# H3BR7.net
KiCad netlist of a schematic drawn in EAGLE
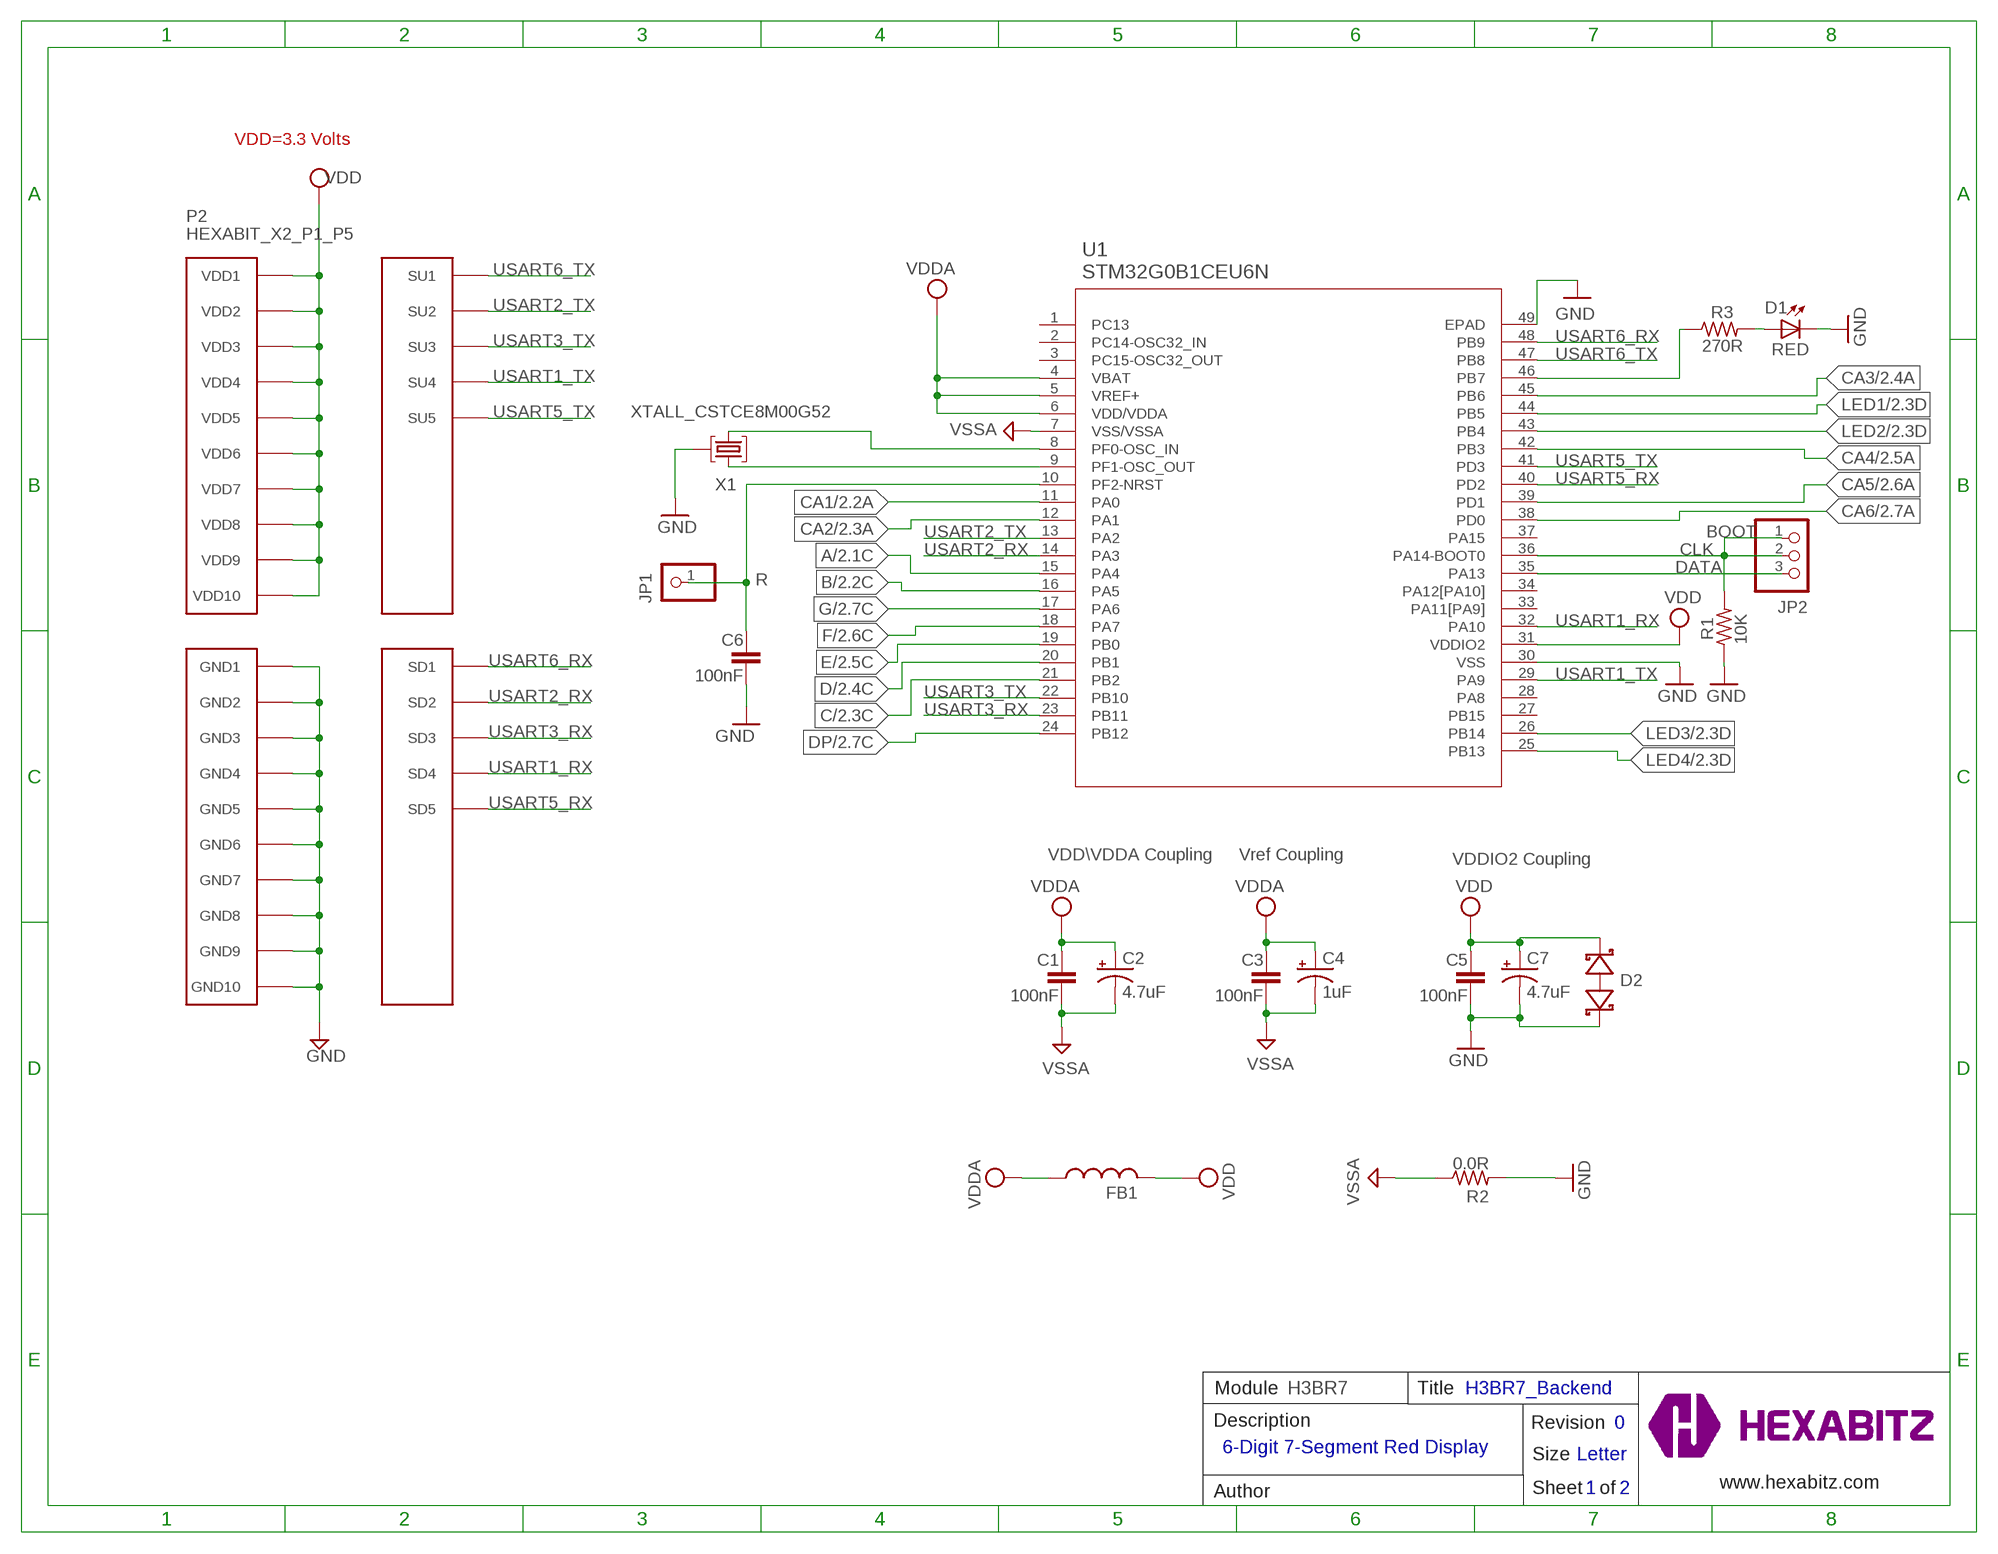
[diagram p0: schematic, sheet 1]
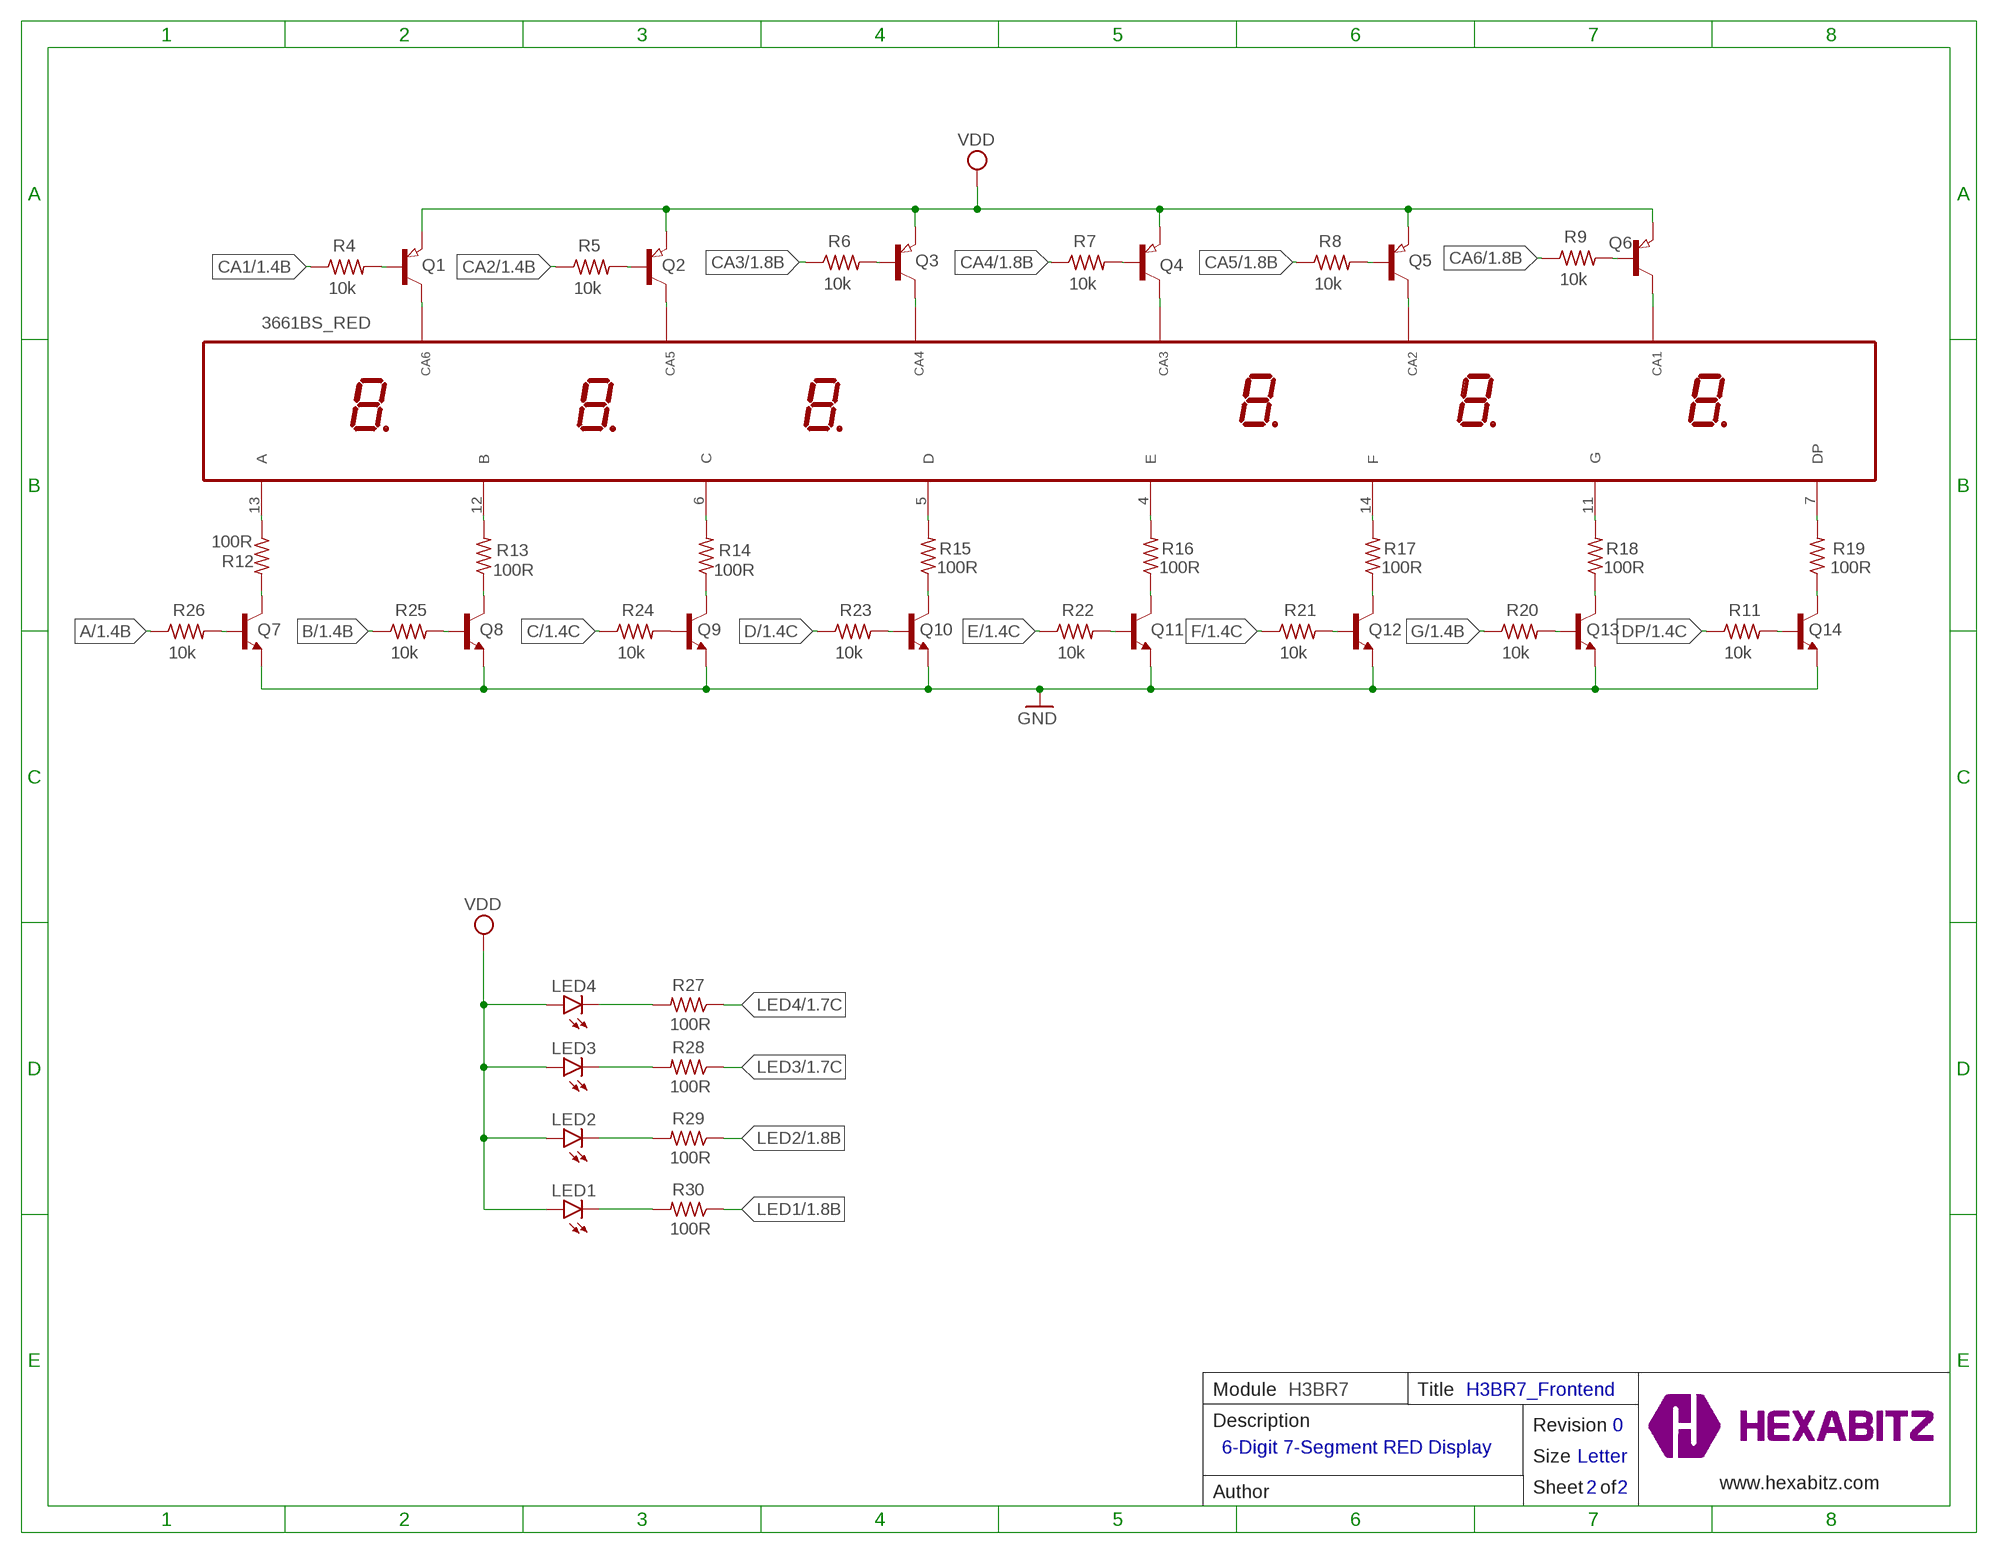
[diagram p1: schematic, sheet 2]

(export (version "E")
  (design (tool "Eeschema 10.0.6"))
  (components
    (comp (ref "3661BS")
      (value "3661BS_RED")
      (footprint "eagle-import:3661BS")
      (libsource (lib "eagle-import") (part "3661BS_RED"))
    )
    (comp (ref "LED1")
      (value "LED-3MM3MM")
      (footprint "eagle-import:LED3MM")
      (libsource (lib "eagle-import") (part "LED-3MM3MM"))
    )
    (comp (ref "LED2")
      (value "LED-3MM3MM")
      (footprint "eagle-import:LED3MM")
      (libsource (lib "eagle-import") (part "LED-3MM3MM"))
    )
    (comp (ref "LED3")
      (value "LED-3MM3MM")
      (footprint "eagle-import:LED3MM")
      (libsource (lib "eagle-import") (part "LED-3MM3MM"))
    )
    (comp (ref "LED4")
      (value "LED-3MM3MM")
      (footprint "eagle-import:LED3MM")
      (libsource (lib "eagle-import") (part "LED-3MM3MM"))
    )
    (comp (ref "Q1")
      (value "SEMICON-SMD-IPC_PNP-TRANSISTOR_SOT23")
      (footprint "eagle-import:SEMICON-SMD-IPC_SOT23")
      (libsource (lib "eagle-import") (part "SEMICON-SMD-IPC_PNP-TRANSISTOR_SOT23"))
    )
    (comp (ref "Q2")
      (value "SEMICON-SMD-IPC_PNP-TRANSISTOR_SOT23")
      (footprint "eagle-import:SEMICON-SMD-IPC_SOT23")
      (libsource (lib "eagle-import") (part "SEMICON-SMD-IPC_PNP-TRANSISTOR_SOT23"))
    )
    (comp (ref "Q3")
      (value "SEMICON-SMD-IPC_PNP-TRANSISTOR_SOT23")
      (footprint "eagle-import:SEMICON-SMD-IPC_SOT23")
      (libsource (lib "eagle-import") (part "SEMICON-SMD-IPC_PNP-TRANSISTOR_SOT23"))
    )
    (comp (ref "Q4")
      (value "SEMICON-SMD-IPC_PNP-TRANSISTOR_SOT23")
      (footprint "eagle-import:SEMICON-SMD-IPC_SOT23")
      (libsource (lib "eagle-import") (part "SEMICON-SMD-IPC_PNP-TRANSISTOR_SOT23"))
    )
    (comp (ref "Q5")
      (value "SEMICON-SMD-IPC_PNP-TRANSISTOR_SOT23")
      (footprint "eagle-import:SEMICON-SMD-IPC_SOT23")
      (libsource (lib "eagle-import") (part "SEMICON-SMD-IPC_PNP-TRANSISTOR_SOT23"))
    )
    (comp (ref "Q6")
      (value "SEMICON-SMD-IPC_PNP-TRANSISTOR_SOT23")
      (footprint "eagle-import:SEMICON-SMD-IPC_SOT23")
      (libsource (lib "eagle-import") (part "SEMICON-SMD-IPC_PNP-TRANSISTOR_SOT23"))
    )
    (comp (ref "Q7")
      (value "MMBT3904LT1")
      (footprint "eagle-import:MMBT3904LT1")
      (libsource (lib "eagle-import") (part "MMBT3904LT1"))
    )
    (comp (ref "Q8")
      (value "MMBT3904LT1")
      (footprint "eagle-import:MMBT3904LT1")
      (libsource (lib "eagle-import") (part "MMBT3904LT1"))
    )
    (comp (ref "Q9")
      (value "MMBT3904LT1")
      (footprint "eagle-import:MMBT3904LT1")
      (libsource (lib "eagle-import") (part "MMBT3904LT1"))
    )
    (comp (ref "Q10")
      (value "MMBT3904LT1")
      (footprint "eagle-import:MMBT3904LT1")
      (libsource (lib "eagle-import") (part "MMBT3904LT1"))
    )
    (comp (ref "Q11")
      (value "MMBT3904LT1")
      (footprint "eagle-import:MMBT3904LT1")
      (libsource (lib "eagle-import") (part "MMBT3904LT1"))
    )
    (comp (ref "Q12")
      (value "MMBT3904LT1")
      (footprint "eagle-import:MMBT3904LT1")
      (libsource (lib "eagle-import") (part "MMBT3904LT1"))
    )
    (comp (ref "Q13")
      (value "MMBT3904LT1")
      (footprint "eagle-import:MMBT3904LT1")
      (libsource (lib "eagle-import") (part "MMBT3904LT1"))
    )
    (comp (ref "Q14")
      (value "MMBT3904LT1")
      (footprint "eagle-import:MMBT3904LT1")
      (libsource (lib "eagle-import") (part "MMBT3904LT1"))
    )
    (comp (ref "R4")
      (value "10k")
      (footprint "eagle-import:R-0603")
      (libsource (lib "eagle-import") (part "R-0603"))
    )
    (comp (ref "R5")
      (value "10k")
      (footprint "eagle-import:R-0603")
      (libsource (lib "eagle-import") (part "R-0603"))
    )
    (comp (ref "R6")
      (value "10k")
      (footprint "eagle-import:R-0603")
      (libsource (lib "eagle-import") (part "R-0603"))
    )
    (comp (ref "R7")
      (value "10k")
      (footprint "eagle-import:R-0603")
      (libsource (lib "eagle-import") (part "R-0603"))
    )
    (comp (ref "R8")
      (value "10k")
      (footprint "eagle-import:R-0603")
      (libsource (lib "eagle-import") (part "R-0603"))
    )
    (comp (ref "R9")
      (value "10k")
      (footprint "eagle-import:R-0603")
      (libsource (lib "eagle-import") (part "R-0603"))
    )
    (comp (ref "R11")
      (value "10k")
      (footprint "eagle-import:R-0603")
      (libsource (lib "eagle-import") (part "R-0603"))
    )
    (comp (ref "R12")
      (value "100R")
      (footprint "eagle-import:R-0603")
      (libsource (lib "eagle-import") (part "R-0603"))
    )
    (comp (ref "R13")
      (value "100R")
      (footprint "eagle-import:R-0603")
      (libsource (lib "eagle-import") (part "R-0603"))
    )
    (comp (ref "R14")
      (value "100R")
      (footprint "eagle-import:R-0603")
      (libsource (lib "eagle-import") (part "R-0603"))
    )
    (comp (ref "R15")
      (value "100R")
      (footprint "eagle-import:R-0603")
      (libsource (lib "eagle-import") (part "R-0603"))
    )
    (comp (ref "R16")
      (value "100R")
      (footprint "eagle-import:R-0603")
      (libsource (lib "eagle-import") (part "R-0603"))
    )
    (comp (ref "R17")
      (value "100R")
      (footprint "eagle-import:R-0603")
      (libsource (lib "eagle-import") (part "R-0603"))
    )
    (comp (ref "R18")
      (value "100R")
      (footprint "eagle-import:R-0603")
      (libsource (lib "eagle-import") (part "R-0603"))
    )
    (comp (ref "R19")
      (value "100R")
      (footprint "eagle-import:R-0603")
      (libsource (lib "eagle-import") (part "R-0603"))
    )
    (comp (ref "R20")
      (value "10k")
      (footprint "eagle-import:R-0603")
      (libsource (lib "eagle-import") (part "R-0603"))
    )
    (comp (ref "R21")
      (value "10k")
      (footprint "eagle-import:R-0603")
      (libsource (lib "eagle-import") (part "R-0603"))
    )
    (comp (ref "R22")
      (value "10k")
      (footprint "eagle-import:R-0603")
      (libsource (lib "eagle-import") (part "R-0603"))
    )
    (comp (ref "R23")
      (value "10k")
      (footprint "eagle-import:R-0603")
      (libsource (lib "eagle-import") (part "R-0603"))
    )
    (comp (ref "R24")
      (value "10k")
      (footprint "eagle-import:R-0603")
      (libsource (lib "eagle-import") (part "R-0603"))
    )
    (comp (ref "R25")
      (value "10k")
      (footprint "eagle-import:R-0603")
      (libsource (lib "eagle-import") (part "R-0603"))
    )
    (comp (ref "R26")
      (value "10k")
      (footprint "eagle-import:R-0603")
      (libsource (lib "eagle-import") (part "R-0603"))
    )
    (comp (ref "R27")
      (value "100R")
      (footprint "eagle-import:R-0603")
      (libsource (lib "eagle-import") (part "R-0603"))
    )
    (comp (ref "R28")
      (value "100R")
      (footprint "eagle-import:R-0603")
      (libsource (lib "eagle-import") (part "R-0603"))
    )
    (comp (ref "R29")
      (value "100R")
      (footprint "eagle-import:R-0603")
      (libsource (lib "eagle-import") (part "R-0603"))
    )
    (comp (ref "R30")
      (value "100R")
      (footprint "eagle-import:R-0603")
      (libsource (lib "eagle-import") (part "R-0603"))
    )
    (comp (ref "TRIMBLE-LOGO1")
      (value "HEXA-LOGO")
      (footprint "eagle-import:HEXA-LOGO")
      (libsource (lib "eagle-import") (part "HEXA-LOGO"))
    )
    (comp (ref "C1")
      (value "100nF")
      (footprint "eagle-import:C-0603")
      (libsource (lib "eagle-import") (part "C-0603"))
    )
    (comp (ref "C2")
      (value "4.7uF")
      (footprint "eagle-import:C-0805-POL")
      (libsource (lib "eagle-import") (part "C-0805-POL"))
    )
    (comp (ref "C3")
      (value "100nF")
      (footprint "eagle-import:C-0603")
      (libsource (lib "eagle-import") (part "C-0603"))
    )
    (comp (ref "C4")
      (value "1uF")
      (footprint "eagle-import:C-0805-POL")
      (libsource (lib "eagle-import") (part "C-0805-POL"))
    )
    (comp (ref "C5")
      (value "100nF")
      (footprint "eagle-import:C-0603")
      (libsource (lib "eagle-import") (part "C-0603"))
    )
    (comp (ref "C6")
      (value "100nF")
      (footprint "eagle-import:C-0603")
      (libsource (lib "eagle-import") (part "C-0603"))
    )
    (comp (ref "C7")
      (value "4.7uF")
      (footprint "eagle-import:C-0805-POL")
      (libsource (lib "eagle-import") (part "C-0805-POL"))
    )
    (comp (ref "D1")
      (value "RED")
      (footprint "eagle-import:VLMS1300-GS08")
      (fields
        (field (name "MPN") "VLMS1300-GS08")
        (field (name "MFN") "Vishay")
        (field (name "MPN_1") "VLMS1300-GS08")
        (field (name "OCTOPART_URL") "https://octopart.com/vlms1300-gs08-vishay-21709201?r=sp&s=_gcP4_q8T1SC6PJQPTQ9yA")
      )
      (libsource (lib "eagle-import") (part "VLMS1300-GS08"))
    )
    (comp (ref "D2")
      (value "BOURNS_CDSOD323-T03SCBOURNS_CDSOD323-T03SC_0_0")
      (footprint "eagle-import:BOURNS_CDSOD323-T03SC_0")
      (fields (field (name "MPN") "CDSOD323-T03SC"))
      (libsource (lib "eagle-import") (part "BOURNS_CDSOD323-T03SCBOURNS_CDSOD323-T03SC_0_0"))
    )
    (comp (ref "FB1")
      (value "FB-0603")
      (footprint "eagle-import:FB-0603")
      (libsource (lib "eagle-import") (part "FB-0603"))
    )
    (comp (ref "JP1")
      (value "R")
      (footprint "eagle-import:1X01")
      (fields (field (name "MPN") "87227-1"))
      (libsource (lib "eagle-import") (part "PINHD-1X1"))
    )
    (comp (ref "JP2")
      (value "PINHD-1X3")
      (footprint "eagle-import:1X03")
      (libsource (lib "eagle-import") (part "PINHD-1X3"))
    )
    (comp (ref "P2")
      (value "HEXABIT_X2_P1_P5")
      (footprint "eagle-import:HEXABIT_17.32_X2_P1_P5")
      (libsource (lib "eagle-import") (part "HEXABIT_X2_P1_P5"))
    )
    (comp (ref "R1")
      (value "10K")
      (footprint "eagle-import:R-0603")
      (libsource (lib "eagle-import") (part "R-0603"))
    )
    (comp (ref "R2")
      (value "0.0R")
      (footprint "eagle-import:R-0603")
      (libsource (lib "eagle-import") (part "R-0603"))
    )
    (comp (ref "R3")
      (value "270R")
      (footprint "eagle-import:R-0603")
      (libsource (lib "eagle-import") (part "R-0603"))
    )
    (comp (ref "U1")
      (value "STM32G0B1CEU6N")
      (footprint "eagle-import:HEXABITZ_ICS_QFN_B1CEU6_STM-L")
      (libsource (lib "eagle-import") (part "STM32G0B1CEU6N"))
    )
    (comp (ref "X1")
      (value "XTALL_CSTCE8M00G52")
      (footprint "eagle-import:XTALL_CSTCE8M00G52")
      (fields (field (name "MPN") "CSTCE8M00G52Z-R0"))
      (libsource (lib "eagle-import") (part "XTALL_CSTCE8M00G52"))
    )
  )
  (nets
    (net (code "1") (name "A") (class "Default")
      (node (ref "R26") (pin "1") (pinfunction "1_1") (pintype "passive"))
      (node (ref "U1") (pin "15") (pinfunction "PA4_15") (pintype "bidirectional"))
    )
    (net (code "2") (name "B") (class "Default")
      (node (ref "R25") (pin "1") (pinfunction "1_1") (pintype "passive"))
      (node (ref "U1") (pin "16") (pinfunction "PA5_16") (pintype "bidirectional"))
    )
    (net (code "3") (name "C") (class "Default")
      (node (ref "R24") (pin "1") (pinfunction "1_1") (pintype "passive"))
      (node (ref "U1") (pin "21") (pinfunction "PB2_21") (pintype "bidirectional"))
    )
    (net (code "4") (name "CA1") (class "Default")
      (node (ref "R4") (pin "1") (pinfunction "1_1") (pintype "passive"))
      (node (ref "U1") (pin "11") (pinfunction "PA0_11") (pintype "bidirectional"))
    )
    (net (code "5") (name "CA2") (class "Default")
      (node (ref "R5") (pin "1") (pinfunction "1_1") (pintype "passive"))
      (node (ref "U1") (pin "12") (pinfunction "PA1_12") (pintype "bidirectional"))
    )
    (net (code "6") (name "CA3") (class "Default")
      (node (ref "R6") (pin "1") (pinfunction "1_1") (pintype "passive"))
      (node (ref "U1") (pin "45") (pinfunction "PB6_45") (pintype "bidirectional"))
    )
    (net (code "7") (name "CA4") (class "Default")
      (node (ref "R7") (pin "1") (pinfunction "1_1") (pintype "passive"))
      (node (ref "U1") (pin "42") (pinfunction "PB3_42") (pintype "bidirectional"))
    )
    (net (code "8") (name "CA5") (class "Default")
      (node (ref "R8") (pin "1") (pinfunction "1_1") (pintype "passive"))
      (node (ref "U1") (pin "39") (pinfunction "PD1_39") (pintype "bidirectional"))
    )
    (net (code "9") (name "CA6") (class "Default")
      (node (ref "R9") (pin "1") (pinfunction "1_1") (pintype "passive"))
      (node (ref "U1") (pin "38") (pinfunction "PD0_38") (pintype "bidirectional"))
    )
    (net (code "10") (name "CLK") (class "Default")
      (node (ref "JP2") (pin "1") (pinfunction "1_1") (pintype "passive"))
      (node (ref "JP2") (pin "2") (pinfunction "2_2") (pintype "passive"))
      (node (ref "R1") (pin "2") (pinfunction "2_2") (pintype "passive"))
      (node (ref "U1") (pin "36") (pinfunction "PA14-BOOT0_36") (pintype "bidirectional"))
    )
    (net (code "11") (name "D") (class "Default")
      (node (ref "R23") (pin "1") (pinfunction "1_1") (pintype "passive"))
      (node (ref "U1") (pin "20") (pinfunction "PB1_20") (pintype "bidirectional"))
    )
    (net (code "12") (name "DATA") (class "Default")
      (node (ref "JP2") (pin "3") (pinfunction "3_3") (pintype "passive"))
      (node (ref "U1") (pin "35") (pinfunction "PA13_35") (pintype "bidirectional"))
    )
    (net (code "13") (name "DP") (class "Default")
      (node (ref "R11") (pin "1") (pinfunction "1_1") (pintype "passive"))
      (node (ref "U1") (pin "24") (pinfunction "PB12_24") (pintype "bidirectional"))
    )
    (net (code "14") (name "E") (class "Default")
      (node (ref "R22") (pin "1") (pinfunction "1_1") (pintype "passive"))
      (node (ref "U1") (pin "19") (pinfunction "PB0_19") (pintype "bidirectional"))
    )
    (net (code "15") (name "F") (class "Default")
      (node (ref "R21") (pin "1") (pinfunction "1_1") (pintype "passive"))
      (node (ref "U1") (pin "18") (pinfunction "PA7_18") (pintype "bidirectional"))
    )
    (net (code "16") (name "G") (class "Default")
      (node (ref "R20") (pin "1") (pinfunction "1_1") (pintype "passive"))
      (node (ref "U1") (pin "17") (pinfunction "PA6_17") (pintype "bidirectional"))
    )
    (net (code "17") (name "GND") (class "Default")
      (node (ref "C5") (pin "2") (pinfunction "2_2") (pintype "passive"))
      (node (ref "C6") (pin "2") (pinfunction "2_2") (pintype "passive"))
      (node (ref "C7") (pin "2") (pinfunction "-_2") (pintype "passive"))
      (node (ref "D1") (pin "C") (pinfunction "C_C") (pintype "passive"))
      (node (ref "D2") (pin "1") (pinfunction "A_1") (pintype "passive"))
      (node (ref "P2") (pin "PAD_PD11") (pinfunction "GND1_PAD_PD11") (pintype "power_in"))
      (node (ref "P2") (pin "PAD_PD12") (pinfunction "GND2_PAD_PD12") (pintype "power_in"))
      (node (ref "P2") (pin "PAD_PD13") (pinfunction "GND3_PAD_PD13") (pintype "power_in"))
      (node (ref "P2") (pin "PAD_PD14") (pinfunction "GND4_PAD_PD14") (pintype "power_in"))
      (node (ref "P2") (pin "PAD_PD15") (pinfunction "GND5_PAD_PD15") (pintype "power_in"))
      (node (ref "P2") (pin "PAD_PD16") (pinfunction "GND6_PAD_PD16") (pintype "power_in"))
      (node (ref "P2") (pin "PAD_PD17") (pinfunction "GND7_PAD_PD17") (pintype "power_in"))
      (node (ref "P2") (pin "PAD_PD18") (pinfunction "GND8_PAD_PD18") (pintype "power_in"))
      (node (ref "P2") (pin "PAD_PD19") (pinfunction "GND9_PAD_PD19") (pintype "power_in"))
      (node (ref "P2") (pin "PAD_PD20") (pinfunction "GND10_PAD_PD20") (pintype "power_in"))
      (node (ref "Q10") (pin "2") (pinfunction "E_2") (pintype "passive"))
      (node (ref "Q11") (pin "2") (pinfunction "E_2") (pintype "passive"))
      (node (ref "Q12") (pin "2") (pinfunction "E_2") (pintype "passive"))
      (node (ref "Q13") (pin "2") (pinfunction "E_2") (pintype "passive"))
      (node (ref "Q14") (pin "2") (pinfunction "E_2") (pintype "passive"))
      (node (ref "Q7") (pin "2") (pinfunction "E_2") (pintype "passive"))
      (node (ref "Q8") (pin "2") (pinfunction "E_2") (pintype "passive"))
      (node (ref "Q9") (pin "2") (pinfunction "E_2") (pintype "passive"))
      (node (ref "R1") (pin "1") (pinfunction "1_1") (pintype "passive"))
      (node (ref "R2") (pin "2") (pinfunction "2_2") (pintype "passive"))
      (node (ref "U1") (pin "30") (pinfunction "VSS_30") (pintype "passive"))
      (node (ref "U1") (pin "49") (pinfunction "EPAD_49") (pintype "passive"))
      (node (ref "X1") (pin "P$2") (pinfunction "2_P$2") (pintype "passive"))
    )
    (net (code "18") (name "LED1") (class "Default")
      (node (ref "R30") (pin "1") (pinfunction "1_1") (pintype "passive"))
      (node (ref "U1") (pin "44") (pinfunction "PB5_44") (pintype "bidirectional"))
    )
    (net (code "19") (name "LED2") (class "Default")
      (node (ref "R29") (pin "1") (pinfunction "1_1") (pintype "passive"))
      (node (ref "U1") (pin "43") (pinfunction "PB4_43") (pintype "bidirectional"))
    )
    (net (code "20") (name "LED3") (class "Default")
      (node (ref "R28") (pin "1") (pinfunction "1_1") (pintype "passive"))
      (node (ref "U1") (pin "26") (pinfunction "PB14_26") (pintype "bidirectional"))
    )
    (net (code "21") (name "LED4") (class "Default")
      (node (ref "R27") (pin "1") (pinfunction "1_1") (pintype "passive"))
      (node (ref "U1") (pin "25") (pinfunction "PB13_25") (pintype "bidirectional"))
    )
    (net (code "22") (name "Net-(3661BS-A)") (class "Default")
      (node (ref "3661BS") (pin "13") (pinfunction "A_13") (pintype "passive"))
      (node (ref "R12") (pin "1") (pinfunction "1_1") (pintype "passive"))
    )
    (net (code "23") (name "Net-(3661BS-B)") (class "Default")
      (node (ref "3661BS") (pin "12") (pinfunction "B_12") (pintype "passive"))
      (node (ref "R13") (pin "2") (pinfunction "2_2") (pintype "passive"))
    )
    (net (code "24") (name "Net-(3661BS-C)") (class "Default")
      (node (ref "3661BS") (pin "6") (pinfunction "C_6") (pintype "passive"))
      (node (ref "R14") (pin "2") (pinfunction "2_2") (pintype "passive"))
    )
    (net (code "25") (name "Net-(3661BS-D)") (class "Default")
      (node (ref "3661BS") (pin "5") (pinfunction "D_5") (pintype "passive"))
      (node (ref "R15") (pin "2") (pinfunction "2_2") (pintype "passive"))
    )
    (net (code "26") (name "Net-(3661BS-DP)") (class "Default")
      (node (ref "3661BS") (pin "7") (pinfunction "DP_7") (pintype "passive"))
      (node (ref "R19") (pin "2") (pinfunction "2_2") (pintype "passive"))
    )
    (net (code "27") (name "Net-(3661BS-E)") (class "Default")
      (node (ref "3661BS") (pin "4") (pinfunction "E_4") (pintype "passive"))
      (node (ref "R16") (pin "2") (pinfunction "2_2") (pintype "passive"))
    )
    (net (code "28") (name "Net-(3661BS-F)") (class "Default")
      (node (ref "3661BS") (pin "14") (pinfunction "F_14") (pintype "passive"))
      (node (ref "R17") (pin "2") (pinfunction "2_2") (pintype "passive"))
    )
    (net (code "29") (name "Net-(3661BS-G)") (class "Default")
      (node (ref "3661BS") (pin "11") (pinfunction "G_11") (pintype "passive"))
      (node (ref "R18") (pin "2") (pinfunction "2_2") (pintype "passive"))
    )
    (net (code "30") (name "Net-(D1-PadA)") (class "Default")
      (node (ref "D1") (pin "A") (pinfunction "A_A") (pintype "passive"))
      (node (ref "R3") (pin "2") (pinfunction "2_2") (pintype "passive"))
    )
    (net (code "31") (name "Net-(LED1-C)") (class "Default")
      (node (ref "LED1") (pin "K") (pinfunction "C_K") (pintype "passive"))
      (node (ref "R30") (pin "2") (pinfunction "2_2") (pintype "passive"))
    )
    (net (code "32") (name "Net-(LED2-C)") (class "Default")
      (node (ref "LED2") (pin "K") (pinfunction "C_K") (pintype "passive"))
      (node (ref "R29") (pin "2") (pinfunction "2_2") (pintype "passive"))
    )
    (net (code "33") (name "Net-(LED3-C)") (class "Default")
      (node (ref "LED3") (pin "K") (pinfunction "C_K") (pintype "passive"))
      (node (ref "R28") (pin "2") (pinfunction "2_2") (pintype "passive"))
    )
    (net (code "34") (name "Net-(LED4-C)") (class "Default")
      (node (ref "LED4") (pin "K") (pinfunction "C_K") (pintype "passive"))
      (node (ref "R27") (pin "2") (pinfunction "2_2") (pintype "passive"))
    )
    (net (code "35") (name "Net-(Q1-B)") (class "Default")
      (node (ref "Q1") (pin "1") (pinfunction "B_1") (pintype "passive"))
      (node (ref "R4") (pin "2") (pinfunction "2_2") (pintype "passive"))
    )
    (net (code "36") (name "Net-(Q1-C)") (class "Default")
      (node (ref "3661BS") (pin "8") (pinfunction "CA_8") (pintype "passive"))
      (node (ref "Q1") (pin "3") (pinfunction "C_3") (pintype "passive"))
    )
    (net (code "37") (name "Net-(Q2-B)") (class "Default")
      (node (ref "Q2") (pin "1") (pinfunction "B_1") (pintype "passive"))
      (node (ref "R5") (pin "2") (pinfunction "2_2") (pintype "passive"))
    )
    (net (code "38") (name "Net-(Q2-C)") (class "Default")
      (node (ref "3661BS") (pin "9") (pinfunction "CA_9") (pintype "passive"))
      (node (ref "Q2") (pin "3") (pinfunction "C_3") (pintype "passive"))
    )
    (net (code "39") (name "Net-(Q3-B)") (class "Default")
      (node (ref "Q3") (pin "1") (pinfunction "B_1") (pintype "passive"))
      (node (ref "R6") (pin "2") (pinfunction "2_2") (pintype "passive"))
    )
    (net (code "40") (name "Net-(Q3-C)") (class "Default")
      (node (ref "3661BS") (pin "10") (pinfunction "CA_10") (pintype "passive"))
      (node (ref "Q3") (pin "3") (pinfunction "C_3") (pintype "passive"))
    )
    (net (code "41") (name "Net-(Q4-B)") (class "Default")
      (node (ref "Q4") (pin "1") (pinfunction "B_1") (pintype "passive"))
      (node (ref "R7") (pin "2") (pinfunction "2_2") (pintype "passive"))
    )
    (net (code "42") (name "Net-(Q4-C)") (class "Default")
      (node (ref "3661BS") (pin "3") (pinfunction "CA_3") (pintype "passive"))
      (node (ref "Q4") (pin "3") (pinfunction "C_3") (pintype "passive"))
    )
    (net (code "43") (name "Net-(Q5-B)") (class "Default")
      (node (ref "Q5") (pin "1") (pinfunction "B_1") (pintype "passive"))
      (node (ref "R8") (pin "2") (pinfunction "2_2") (pintype "passive"))
    )
    (net (code "44") (name "Net-(Q5-C)") (class "Default")
      (node (ref "3661BS") (pin "2") (pinfunction "CA_2") (pintype "passive"))
      (node (ref "Q5") (pin "3") (pinfunction "C_3") (pintype "passive"))
    )
    (net (code "45") (name "Net-(Q6-B)") (class "Default")
      (node (ref "Q6") (pin "1") (pinfunction "B_1") (pintype "passive"))
      (node (ref "R9") (pin "2") (pinfunction "2_2") (pintype "passive"))
    )
    (net (code "46") (name "Net-(Q6-C)") (class "Default")
      (node (ref "3661BS") (pin "1") (pinfunction "CA_1") (pintype "passive"))
      (node (ref "Q6") (pin "3") (pinfunction "C_3") (pintype "passive"))
    )
    (net (code "47") (name "Net-(Q7-B)") (class "Default")
      (node (ref "Q7") (pin "1") (pinfunction "B_1") (pintype "passive"))
      (node (ref "R26") (pin "2") (pinfunction "2_2") (pintype "passive"))
    )
    (net (code "48") (name "Net-(Q7-C)") (class "Default")
      (node (ref "Q7") (pin "3") (pinfunction "C_3") (pintype "passive"))
      (node (ref "R12") (pin "2") (pinfunction "2_2") (pintype "passive"))
    )
    (net (code "49") (name "Net-(Q8-B)") (class "Default")
      (node (ref "Q8") (pin "1") (pinfunction "B_1") (pintype "passive"))
      (node (ref "R25") (pin "2") (pinfunction "2_2") (pintype "passive"))
    )
    (net (code "50") (name "Net-(Q8-C)") (class "Default")
      (node (ref "Q8") (pin "3") (pinfunction "C_3") (pintype "passive"))
      (node (ref "R13") (pin "1") (pinfunction "1_1") (pintype "passive"))
    )
    (net (code "51") (name "Net-(Q9-B)") (class "Default")
      (node (ref "Q9") (pin "1") (pinfunction "B_1") (pintype "passive"))
      (node (ref "R24") (pin "2") (pinfunction "2_2") (pintype "passive"))
    )
    (net (code "52") (name "Net-(Q9-C)") (class "Default")
      (node (ref "Q9") (pin "3") (pinfunction "C_3") (pintype "passive"))
      (node (ref "R14") (pin "1") (pinfunction "1_1") (pintype "passive"))
    )
    (net (code "53") (name "Net-(Q10-B)") (class "Default")
      (node (ref "Q10") (pin "1") (pinfunction "B_1") (pintype "passive"))
      (node (ref "R23") (pin "2") (pinfunction "2_2") (pintype "passive"))
    )
    (net (code "54") (name "Net-(Q10-C)") (class "Default")
      (node (ref "Q10") (pin "3") (pinfunction "C_3") (pintype "passive"))
      (node (ref "R15") (pin "1") (pinfunction "1_1") (pintype "passive"))
    )
    (net (code "55") (name "Net-(Q11-B)") (class "Default")
      (node (ref "Q11") (pin "1") (pinfunction "B_1") (pintype "passive"))
      (node (ref "R22") (pin "2") (pinfunction "2_2") (pintype "passive"))
    )
    (net (code "56") (name "Net-(Q11-C)") (class "Default")
      (node (ref "Q11") (pin "3") (pinfunction "C_3") (pintype "passive"))
      (node (ref "R16") (pin "1") (pinfunction "1_1") (pintype "passive"))
    )
    (net (code "57") (name "Net-(Q12-B)") (class "Default")
      (node (ref "Q12") (pin "1") (pinfunction "B_1") (pintype "passive"))
      (node (ref "R21") (pin "2") (pinfunction "2_2") (pintype "passive"))
    )
    (net (code "58") (name "Net-(Q12-C)") (class "Default")
      (node (ref "Q12") (pin "3") (pinfunction "C_3") (pintype "passive"))
      (node (ref "R17") (pin "1") (pinfunction "1_1") (pintype "passive"))
    )
    (net (code "59") (name "Net-(Q13-B)") (class "Default")
      (node (ref "Q13") (pin "1") (pinfunction "B_1") (pintype "passive"))
      (node (ref "R20") (pin "2") (pinfunction "2_2") (pintype "passive"))
    )
    (net (code "60") (name "Net-(Q13-C)") (class "Default")
      (node (ref "Q13") (pin "3") (pinfunction "C_3") (pintype "passive"))
      (node (ref "R18") (pin "1") (pinfunction "1_1") (pintype "passive"))
    )
    (net (code "61") (name "Net-(Q14-B)") (class "Default")
      (node (ref "Q14") (pin "1") (pinfunction "B_1") (pintype "passive"))
      (node (ref "R11") (pin "2") (pinfunction "2_2") (pintype "passive"))
    )
    (net (code "62") (name "Net-(Q14-C)") (class "Default")
      (node (ref "Q14") (pin "3") (pinfunction "C_3") (pintype "passive"))
      (node (ref "R19") (pin "1") (pinfunction "1_1") (pintype "passive"))
    )
    (net (code "63") (name "Net-(U1-PB7)") (class "Default")
      (node (ref "R3") (pin "1") (pinfunction "1_1") (pintype "passive"))
      (node (ref "U1") (pin "46") (pinfunction "PB7_46") (pintype "bidirectional"))
    )
    (net (code "64") (name "Net-(U1-PF0-OSC_IN)") (class "Default")
      (node (ref "U1") (pin "8") (pinfunction "PF0-OSC_IN_8") (pintype "bidirectional"))
      (node (ref "X1") (pin "P$3") (pinfunction "3_P$3") (pintype "passive"))
    )
    (net (code "65") (name "Net-(U1-PF1-OSC_OUT)") (class "Default")
      (node (ref "U1") (pin "9") (pinfunction "PF1-OSC_OUT_9") (pintype "bidirectional"))
      (node (ref "X1") (pin "P$1") (pinfunction "1_P$1") (pintype "passive"))
    )
    (net (code "66") (name "Net-(U1-PF2-NRST)") (class "Default")
      (node (ref "C6") (pin "1") (pinfunction "1_1") (pintype "passive"))
      (node (ref "JP1") (pin "1") (pinfunction "1_1") (pintype "passive"))
      (node (ref "U1") (pin "10") (pinfunction "PF2-NRST_10") (pintype "bidirectional"))
    )
    (net (code "67") (name "USART1_RX") (class "Default")
      (node (ref "P2") (pin "PAD_PD4") (pinfunction "SD4_PAD_PD4") (pintype "bidirectional"))
      (node (ref "U1") (pin "32") (pinfunction "PA10_32") (pintype "bidirectional"))
    )
    (net (code "68") (name "USART1_TX") (class "Default")
      (node (ref "P2") (pin "PAD_PU4") (pinfunction "SU4_PAD_PU4") (pintype "bidirectional"))
      (node (ref "U1") (pin "29") (pinfunction "PA9_29") (pintype "bidirectional"))
    )
    (net (code "69") (name "USART2_RX") (class "Default")
      (node (ref "P2") (pin "PAD_PD2") (pinfunction "SD2_PAD_PD2") (pintype "bidirectional"))
      (node (ref "U1") (pin "14") (pinfunction "PA3_14") (pintype "bidirectional"))
    )
    (net (code "70") (name "USART2_TX") (class "Default")
      (node (ref "P2") (pin "PAD_PU2") (pinfunction "SU2_PAD_PU2") (pintype "bidirectional"))
      (node (ref "U1") (pin "13") (pinfunction "PA2_13") (pintype "bidirectional"))
    )
    (net (code "71") (name "USART3_RX") (class "Default")
      (node (ref "P2") (pin "PAD_PD3") (pinfunction "SD3_PAD_PD3") (pintype "bidirectional"))
      (node (ref "U1") (pin "23") (pinfunction "PB11_23") (pintype "bidirectional"))
    )
    (net (code "72") (name "USART3_TX") (class "Default")
      (node (ref "P2") (pin "PAD_PU3") (pinfunction "SU3_PAD_PU3") (pintype "bidirectional"))
      (node (ref "U1") (pin "22") (pinfunction "PB10_22") (pintype "bidirectional"))
    )
    (net (code "73") (name "USART5_RX") (class "Default")
      (node (ref "P2") (pin "PAD_PD5") (pinfunction "SD5_PAD_PD5") (pintype "bidirectional"))
      (node (ref "U1") (pin "40") (pinfunction "PD2_40") (pintype "bidirectional"))
    )
    (net (code "74") (name "USART5_TX") (class "Default")
      (node (ref "P2") (pin "PAD_PU5") (pinfunction "SU5_PAD_PU5") (pintype "bidirectional"))
      (node (ref "U1") (pin "41") (pinfunction "PD3_41") (pintype "bidirectional"))
    )
    (net (code "75") (name "USART6_RX") (class "Default")
      (node (ref "P2") (pin "PAD_PD1") (pinfunction "SD1_PAD_PD1") (pintype "bidirectional"))
      (node (ref "U1") (pin "48") (pinfunction "PB9_48") (pintype "bidirectional"))
    )
    (net (code "76") (name "USART6_TX") (class "Default")
      (node (ref "P2") (pin "PAD_PU1") (pinfunction "SU1_PAD_PU1") (pintype "bidirectional"))
      (node (ref "U1") (pin "47") (pinfunction "PB8_47") (pintype "bidirectional"))
    )
    (net (code "77") (name "VDD") (class "Default")
      (node (ref "C5") (pin "1") (pinfunction "1_1") (pintype "passive"))
      (node (ref "C7") (pin "1") (pinfunction "+_1") (pintype "passive"))
      (node (ref "D2") (pin "2") (pinfunction "C_2") (pintype "passive"))
      (node (ref "FB1") (pin "2") (pinfunction "2_2") (pintype "passive"))
      (node (ref "LED1") (pin "A") (pinfunction "A_A") (pintype "passive"))
      (node (ref "LED2") (pin "A") (pinfunction "A_A") (pintype "passive"))
      (node (ref "LED3") (pin "A") (pinfunction "A_A") (pintype "passive"))
      (node (ref "LED4") (pin "A") (pinfunction "A_A") (pintype "passive"))
      (node (ref "P2") (pin "PAD_PU11") (pinfunction "VDD1_PAD_PU11") (pintype "power_in"))
      (node (ref "P2") (pin "PAD_PU12") (pinfunction "VDD2_PAD_PU12") (pintype "power_in"))
      (node (ref "P2") (pin "PAD_PU13") (pinfunction "VDD3_PAD_PU13") (pintype "power_in"))
      (node (ref "P2") (pin "PAD_PU14") (pinfunction "VDD4_PAD_PU14") (pintype "power_in"))
      (node (ref "P2") (pin "PAD_PU15") (pinfunction "VDD5_PAD_PU15") (pintype "power_in"))
      (node (ref "P2") (pin "PAD_PU16") (pinfunction "VDD6_PAD_PU16") (pintype "power_in"))
      (node (ref "P2") (pin "PAD_PU17") (pinfunction "VDD7_PAD_PU17") (pintype "power_in"))
      (node (ref "P2") (pin "PAD_PU18") (pinfunction "VDD8_PAD_PU18") (pintype "power_in"))
      (node (ref "P2") (pin "PAD_PU19") (pinfunction "VDD9_PAD_PU19") (pintype "power_in"))
      (node (ref "P2") (pin "PAD_PU20") (pinfunction "VDD10_PAD_PU20") (pintype "power_in"))
      (node (ref "Q1") (pin "2") (pinfunction "E_2") (pintype "passive"))
      (node (ref "Q2") (pin "2") (pinfunction "E_2") (pintype "passive"))
      (node (ref "Q3") (pin "2") (pinfunction "E_2") (pintype "passive"))
      (node (ref "Q4") (pin "2") (pinfunction "E_2") (pintype "passive"))
      (node (ref "Q5") (pin "2") (pinfunction "E_2") (pintype "passive"))
      (node (ref "Q6") (pin "2") (pinfunction "E_2") (pintype "passive"))
      (node (ref "U1") (pin "31") (pinfunction "VDDIO2_31") (pintype "power_in"))
    )
    (net (code "78") (name "VDDA") (class "Default")
      (node (ref "C1") (pin "1") (pinfunction "1_1") (pintype "passive"))
      (node (ref "C2") (pin "1") (pinfunction "+_1") (pintype "passive"))
      (node (ref "C3") (pin "1") (pinfunction "1_1") (pintype "passive"))
      (node (ref "C4") (pin "1") (pinfunction "+_1") (pintype "passive"))
      (node (ref "FB1") (pin "1") (pinfunction "1_1") (pintype "passive"))
      (node (ref "U1") (pin "4") (pinfunction "VBAT_4") (pintype "power_in"))
      (node (ref "U1") (pin "5") (pinfunction "VREF+_5") (pintype "power_in"))
      (node (ref "U1") (pin "6") (pinfunction "VDD/VDDA_6") (pintype "power_in"))
    )
    (net (code "79") (name "VSSA") (class "Default")
      (node (ref "C1") (pin "2") (pinfunction "2_2") (pintype "passive"))
      (node (ref "C2") (pin "2") (pinfunction "-_2") (pintype "passive"))
      (node (ref "C3") (pin "2") (pinfunction "2_2") (pintype "passive"))
      (node (ref "C4") (pin "2") (pinfunction "-_2") (pintype "passive"))
      (node (ref "R2") (pin "1") (pinfunction "1_1") (pintype "passive"))
      (node (ref "U1") (pin "7") (pinfunction "VSS/VSSA_7") (pintype "passive"))
    )
    (net (code "80") (name "unconnected-(U1-PA8-Pad28)") (class "Default")
      (node (ref "U1") (pin "28") (pinfunction "PA8_28") (pintype "bidirectional"))
    )
    (net (code "81") (name "unconnected-(U1-PA11[PA9]-Pad33)") (class "Default")
      (node (ref "U1") (pin "33") (pinfunction "PA11[PA9]_33") (pintype "bidirectional"))
    )
    (net (code "82") (name "unconnected-(U1-PA12[PA10]-Pad34)") (class "Default")
      (node (ref "U1") (pin "34") (pinfunction "PA12[PA10]_34") (pintype "bidirectional"))
    )
    (net (code "83") (name "unconnected-(U1-PA15-Pad37)") (class "Default")
      (node (ref "U1") (pin "37") (pinfunction "PA15_37") (pintype "bidirectional"))
    )
    (net (code "84") (name "unconnected-(U1-PB15-Pad27)") (class "Default")
      (node (ref "U1") (pin "27") (pinfunction "PB15_27") (pintype "bidirectional"))
    )
    (net (code "85") (name "unconnected-(U1-PC13-Pad1)") (class "Default")
      (node (ref "U1") (pin "1") (pinfunction "PC13_1") (pintype "bidirectional"))
    )
    (net (code "86") (name "unconnected-(U1-PC14-OSC32_IN-Pad2)") (class "Default")
      (node (ref "U1") (pin "2") (pinfunction "PC14-OSC32_IN_2") (pintype "bidirectional"))
    )
    (net (code "87") (name "unconnected-(U1-PC15-OSC32_OUT-Pad3)") (class "Default")
      (node (ref "U1") (pin "3") (pinfunction "PC15-OSC32_OUT_3") (pintype "bidirectional"))
    )
  )
)
